# out_board.net
KiCad netlist of a schematic drawn in EAGLE
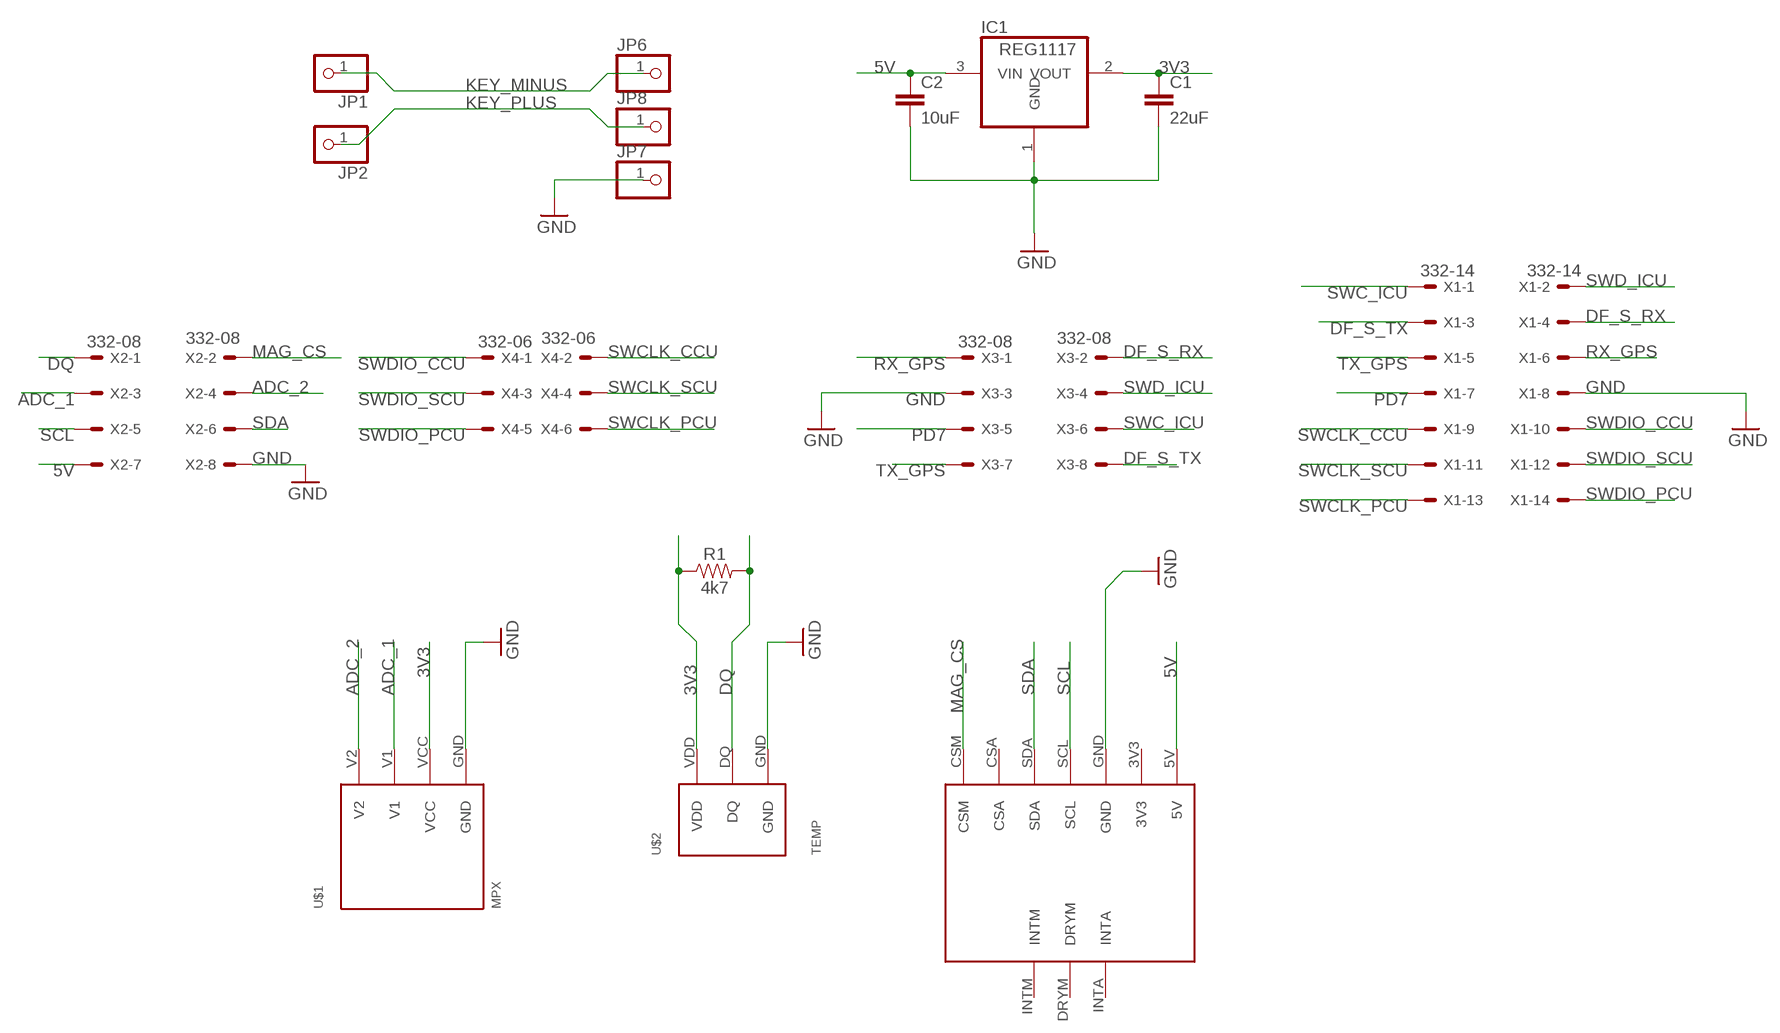
[diagram p0: schematic, sheet 1]

(export (version "E")
  (design (tool "Eeschema 10.0.6"))
  (components
    (comp (ref "C1")
      (value "22uF")
      (footprint "eagle-import:0805")
      (libsource (lib "eagle-import") (part "22UF-0805-6.3V-20%"))
    )
    (comp (ref "C2")
      (value "10uF")
      (footprint "eagle-import:0805")
      (libsource (lib "eagle-import") (part "22UF-0805-16V-20%"))
    )
    (comp (ref "IC1")
      (value "REG1117")
      (footprint "eagle-import:SOT223")
      (libsource (lib "eagle-import") (part "REG1117"))
    )
    (comp (ref "JP1")
      (value "PINHD-1X1")
      (footprint "eagle-import:1X01")
      (libsource (lib "eagle-import") (part "PINHD-1X1"))
    )
    (comp (ref "JP2")
      (value "PINHD-1X1")
      (footprint "eagle-import:1X01")
      (libsource (lib "eagle-import") (part "PINHD-1X1"))
    )
    (comp (ref "JP6")
      (value "PINHD-1X1")
      (footprint "eagle-import:1X01")
      (libsource (lib "eagle-import") (part "PINHD-1X1"))
    )
    (comp (ref "JP7")
      (value "PINHD-1X1")
      (footprint "eagle-import:1X01")
      (libsource (lib "eagle-import") (part "PINHD-1X1"))
    )
    (comp (ref "JP8")
      (value "PINHD-1X1")
      (footprint "eagle-import:1X01")
      (libsource (lib "eagle-import") (part "PINHD-1X1"))
    )
    (comp (ref "R1")
      (value "4k7")
      (footprint "eagle-import:AXIAL-0.3")
      (libsource (lib "eagle-import") (part "RESISTORAXIAL-0.3"))
    )
    (comp (ref "U$1")
      (value "MPX")
      (footprint "eagle-import:MPX")
      (libsource (lib "eagle-import") (part "MPX"))
    )
    (comp (ref "U$2")
      (value "TEMP")
      (footprint "eagle-import:TEMP")
      (libsource (lib "eagle-import") (part "TEMP"))
    )
    (comp (ref "U$3")
      (value "LSM303C")
      (footprint "eagle-import:LSM303C")
      (libsource (lib "eagle-import") (part "LSM303C"))
    )
    (comp (ref "X1")
      (value "332-14")
      (footprint "eagle-import:332-14")
      (libsource (lib "eagle-import") (part "332-14"))
    )
    (comp (ref "X2")
      (value "332-08")
      (footprint "eagle-import:332-08")
      (libsource (lib "eagle-import") (part "332-08"))
    )
    (comp (ref "X3")
      (value "332-08")
      (footprint "eagle-import:332-08")
      (libsource (lib "eagle-import") (part "332-08"))
    )
    (comp (ref "X4")
      (value "332-06")
      (footprint "eagle-import:332-06")
      (libsource (lib "eagle-import") (part "332-06"))
    )
  )
  (nets
    (net (code "1") (name "/3V3") (class "Default")
      (node (ref "C1") (pin "1") (pinfunction "1_1") (pintype "passive"))
      (node (ref "IC1") (pin "2") (pinfunction "VOUT_2") (pintype "output"))
      (node (ref "R1") (pin "P$1") (pinfunction "1_P$1") (pintype "passive"))
      (node (ref "U$1") (pin "VCC") (pinfunction "VCC_VCC") (pintype "bidirectional"))
      (node (ref "U$2") (pin "VDD") (pinfunction "VDD_VDD") (pintype "bidirectional"))
    )
    (net (code "2") (name "/5V") (class "Default")
      (node (ref "C2") (pin "1") (pinfunction "1_1") (pintype "passive"))
      (node (ref "IC1") (pin "3") (pinfunction "VIN_3") (pintype "input"))
      (node (ref "U$3") (pin "5V") (pinfunction "5V_5V") (pintype "bidirectional"))
      (node (ref "X2") (pin "7") (pinfunction "S_7") (pintype "passive"))
    )
    (net (code "3") (name "/ADC_1") (class "Default")
      (node (ref "U$1") (pin "V1") (pinfunction "V1_V1") (pintype "bidirectional"))
      (node (ref "X2") (pin "3") (pinfunction "S_3") (pintype "passive"))
    )
    (net (code "4") (name "/ADC_2") (class "Default")
      (node (ref "U$1") (pin "V2") (pinfunction "V2_V2") (pintype "bidirectional"))
      (node (ref "X2") (pin "4") (pinfunction "S_4") (pintype "passive"))
    )
    (net (code "5") (name "/DF_S_RX") (class "Default")
      (node (ref "X1") (pin "4") (pinfunction "S_4") (pintype "passive"))
      (node (ref "X3") (pin "2") (pinfunction "S_2") (pintype "passive"))
    )
    (net (code "6") (name "/DF_S_TX") (class "Default")
      (node (ref "X1") (pin "3") (pinfunction "S_3") (pintype "passive"))
      (node (ref "X3") (pin "8") (pinfunction "S_8") (pintype "passive"))
    )
    (net (code "7") (name "/DQ") (class "Default")
      (node (ref "R1") (pin "P$2") (pinfunction "2_P$2") (pintype "passive"))
      (node (ref "U$2") (pin "DQ") (pinfunction "DQ_DQ") (pintype "bidirectional"))
      (node (ref "X2") (pin "1") (pinfunction "S_1") (pintype "passive"))
    )
    (net (code "8") (name "/KEY_MINUS") (class "Default")
      (node (ref "JP1") (pin "1") (pinfunction "1_1") (pintype "passive"))
      (node (ref "JP6") (pin "1") (pinfunction "1_1") (pintype "passive"))
    )
    (net (code "9") (name "/KEY_PLUS") (class "Default")
      (node (ref "JP2") (pin "1") (pinfunction "1_1") (pintype "passive"))
      (node (ref "JP8") (pin "1") (pinfunction "1_1") (pintype "passive"))
    )
    (net (code "10") (name "/MAG_CS") (class "Default")
      (node (ref "U$3") (pin "CSM") (pinfunction "CSM_CSM") (pintype "bidirectional"))
      (node (ref "X2") (pin "2") (pinfunction "S_2") (pintype "passive"))
    )
    (net (code "11") (name "/PD7") (class "Default")
      (node (ref "X1") (pin "7") (pinfunction "S_7") (pintype "passive"))
      (node (ref "X3") (pin "5") (pinfunction "S_5") (pintype "passive"))
    )
    (net (code "12") (name "/RX_GPS") (class "Default")
      (node (ref "X1") (pin "6") (pinfunction "S_6") (pintype "passive"))
      (node (ref "X3") (pin "1") (pinfunction "S_1") (pintype "passive"))
    )
    (net (code "13") (name "/SCL") (class "Default")
      (node (ref "U$3") (pin "SCL") (pinfunction "SCL_SCL") (pintype "bidirectional"))
      (node (ref "X2") (pin "5") (pinfunction "S_5") (pintype "passive"))
    )
    (net (code "14") (name "/SDA") (class "Default")
      (node (ref "U$3") (pin "SDA") (pinfunction "SDA_SDA") (pintype "bidirectional"))
      (node (ref "X2") (pin "6") (pinfunction "S_6") (pintype "passive"))
    )
    (net (code "15") (name "/SWCLK_CCU") (class "Default")
      (node (ref "X1") (pin "9") (pinfunction "S_9") (pintype "passive"))
      (node (ref "X4") (pin "2") (pinfunction "S_2") (pintype "passive"))
    )
    (net (code "16") (name "/SWCLK_PCU") (class "Default")
      (node (ref "X1") (pin "13") (pinfunction "S_13") (pintype "passive"))
      (node (ref "X4") (pin "6") (pinfunction "S_6") (pintype "passive"))
    )
    (net (code "17") (name "/SWCLK_SCU") (class "Default")
      (node (ref "X1") (pin "11") (pinfunction "S_11") (pintype "passive"))
      (node (ref "X4") (pin "4") (pinfunction "S_4") (pintype "passive"))
    )
    (net (code "18") (name "/SWC_ICU") (class "Default")
      (node (ref "X1") (pin "1") (pinfunction "S_1") (pintype "passive"))
      (node (ref "X3") (pin "6") (pinfunction "S_6") (pintype "passive"))
    )
    (net (code "19") (name "/SWDIO_CCU") (class "Default")
      (node (ref "X1") (pin "10") (pinfunction "S_10") (pintype "passive"))
      (node (ref "X4") (pin "1") (pinfunction "S_1") (pintype "passive"))
    )
    (net (code "20") (name "/SWDIO_PCU") (class "Default")
      (node (ref "X1") (pin "14") (pinfunction "S_14") (pintype "passive"))
      (node (ref "X4") (pin "5") (pinfunction "S_5") (pintype "passive"))
    )
    (net (code "21") (name "/SWDIO_SCU") (class "Default")
      (node (ref "X1") (pin "12") (pinfunction "S_12") (pintype "passive"))
      (node (ref "X4") (pin "3") (pinfunction "S_3") (pintype "passive"))
    )
    (net (code "22") (name "/SWD_ICU") (class "Default")
      (node (ref "X1") (pin "2") (pinfunction "S_2") (pintype "passive"))
      (node (ref "X3") (pin "4") (pinfunction "S_4") (pintype "passive"))
    )
    (net (code "23") (name "/TX_GPS") (class "Default")
      (node (ref "X1") (pin "5") (pinfunction "S_5") (pintype "passive"))
      (node (ref "X3") (pin "7") (pinfunction "S_7") (pintype "passive"))
    )
    (net (code "24") (name "GND") (class "Default")
      (node (ref "C1") (pin "2") (pinfunction "2_2") (pintype "passive"))
      (node (ref "C2") (pin "2") (pinfunction "2_2") (pintype "passive"))
      (node (ref "IC1") (pin "1") (pinfunction "GND_1") (pintype "power_in"))
      (node (ref "JP7") (pin "1") (pinfunction "1_1") (pintype "passive"))
      (node (ref "U$1") (pin "GND") (pinfunction "GND_GND") (pintype "bidirectional"))
      (node (ref "U$2") (pin "GND") (pinfunction "GND_GND") (pintype "bidirectional"))
      (node (ref "U$3") (pin "GND") (pinfunction "GND_GND") (pintype "bidirectional"))
      (node (ref "X1") (pin "8") (pinfunction "S_8") (pintype "passive"))
      (node (ref "X2") (pin "8") (pinfunction "S_8") (pintype "passive"))
      (node (ref "X3") (pin "3") (pinfunction "S_3") (pintype "passive"))
    )
    (net (code "25") (name "unconnected-(U$3-Pad3V3)") (class "Default")
      (node (ref "U$3") (pin "3V3") (pinfunction "3V3_3V3") (pintype "bidirectional"))
    )
    (net (code "26") (name "unconnected-(U$3-PadCSA)") (class "Default")
      (node (ref "U$3") (pin "CSA") (pinfunction "CSA_CSA") (pintype "bidirectional"))
    )
    (net (code "27") (name "unconnected-(U$3-PadDRYM)") (class "Default")
      (node (ref "U$3") (pin "DRYM") (pinfunction "DRYM_DRYM") (pintype "bidirectional"))
    )
    (net (code "28") (name "unconnected-(U$3-PadINTA)") (class "Default")
      (node (ref "U$3") (pin "INTA") (pinfunction "INTA_INTA") (pintype "bidirectional"))
    )
    (net (code "29") (name "unconnected-(U$3-PadINTM)") (class "Default")
      (node (ref "U$3") (pin "INTM") (pinfunction "INTM_INTM") (pintype "bidirectional"))
    )
  )
)
